# esquemabasico.net
KiCad netlist of a schematic drawn in EAGLE
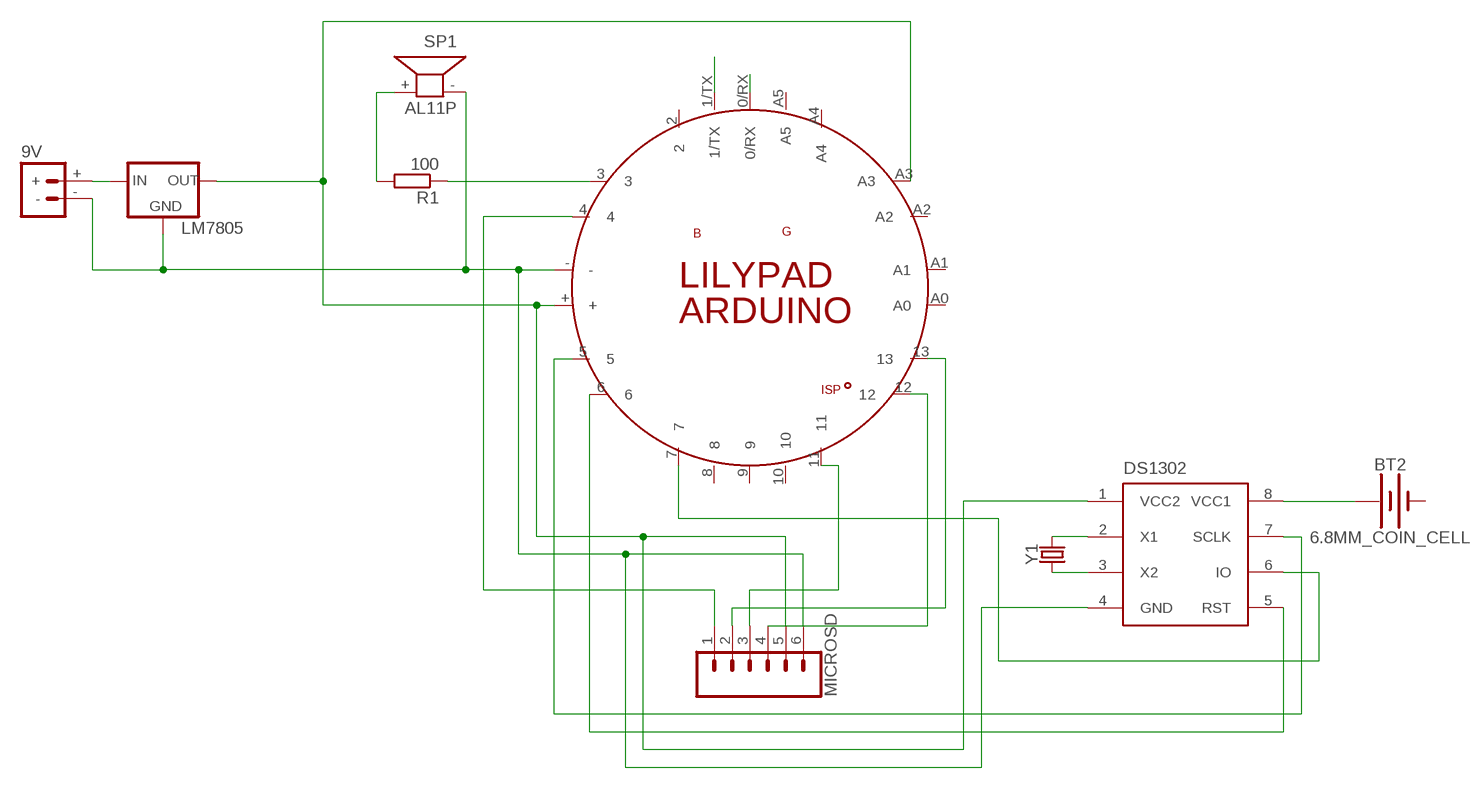
[diagram p0: schematic, sheet 1]

(export (version "E")
  (design (tool "Eeschema 10.0.6"))
  (components
    (comp (ref "9V")
      (value "BATTERY_CONN_DEANS")
      (footprint "eagle-import:DEANS")
      (libsource (lib "eagle-import") (part "BATTERY_CONN_DEANS"))
    )
    (comp (ref "BT2")
      (value "6.8MM_COIN_CELL")
      (footprint "eagle-import:BATTCON-6.8MM")
      (libsource (lib "eagle-import") (part "BATTERY-6.8MM_SMD"))
    )
    (comp (ref "DS1302")
      (value "DS1302")
      (footprint "eagle-import:PDIP8")
      (libsource (lib "eagle-import") (part "DS1302"))
    )
    (comp (ref "LM7805")
      (value "V_REG_78XX-TO-220")
      (footprint "eagle-import:TO-220-ALT")
      (libsource (lib "eagle-import") (part "V_REG_78XX-TO-220"))
    )
    (comp (ref "MICROSD")
      (value "CONN_06FEMALE_LOCK")
      (footprint "eagle-import:1X06_FEMALE_LOCK.010")
      (libsource (lib "eagle-import") (part "CONN_06FEMALE_LOCK"))
    )
    (comp (ref "PCB1")
      (value "ARDUINO_LILYPAD")
      (footprint "eagle-import:ARDUINO_LILYPAD")
      (libsource (lib "eagle-import") (part "ARDUINO_LILYPAD"))
    )
    (comp (ref "R1")
      (value "100")
      (footprint "eagle-import:0309_12")
      (libsource (lib "eagle-import") (part "R-EU_0309/12"))
    )
    (comp (ref "SP1")
      (value "AL11P")
      (footprint "eagle-import:AL11P")
      (libsource (lib "eagle-import") (part "AL11P"))
    )
    (comp (ref "Y1")
      (value "CRYSTALPTH-2X6")
      (footprint "eagle-import:CRYSTAL-PTH-2X6-CYL")
      (libsource (lib "eagle-import") (part "CRYSTALPTH-2X6"))
    )
  )
  (nets
    (net (code "1") (name "/-") (class "Default")
      (node (ref "BT2") (pin "-") (pinfunction "-_-") (pintype "power_in"))
    )
    (net (code "2") (name "Net-(9V-Pad+)") (class "Default")
      (node (ref "9V") (pin "+") (pinfunction "+_+") (pintype "passive"))
      (node (ref "LM7805") (pin "IN") (pinfunction "IN_IN") (pintype "input"))
    )
    (net (code "3") (name "Net-(DS1302-GND)") (class "Default")
      (node (ref "9V") (pin "-") (pinfunction "-_-") (pintype "passive"))
      (node (ref "DS1302") (pin "4") (pinfunction "GND_4") (pintype "power_in"))
      (node (ref "LM7805") (pin "GND") (pinfunction "GND_GND") (pintype "input"))
      (node (ref "MICROSD") (pin "6") (pinfunction "6_6") (pintype "passive"))
      (node (ref "PCB1") (pin "-") (pinfunction "-_-") (pintype "bidirectional"))
      (node (ref "SP1") (pin "-") (pinfunction "1_-") (pintype "passive"))
    )
    (net (code "4") (name "Net-(DS1302-IO)") (class "Default")
      (node (ref "DS1302") (pin "6") (pinfunction "IO_6") (pintype "bidirectional"))
      (node (ref "PCB1") (pin "7") (pinfunction "7_7") (pintype "bidirectional"))
    )
    (net (code "5") (name "Net-(DS1302-RST)") (class "Default")
      (node (ref "DS1302") (pin "5") (pinfunction "RST_5") (pintype "input"))
      (node (ref "PCB1") (pin "6") (pinfunction "6_6") (pintype "bidirectional"))
    )
    (net (code "6") (name "Net-(DS1302-SCLK)") (class "Default")
      (node (ref "DS1302") (pin "7") (pinfunction "SCLK_7") (pintype "input"))
      (node (ref "PCB1") (pin "5") (pinfunction "5_5") (pintype "bidirectional"))
    )
    (net (code "7") (name "Net-(DS1302-VCC1)") (class "Default")
      (node (ref "BT2") (pin "+") (pinfunction "+_+") (pintype "power_in"))
      (node (ref "DS1302") (pin "8") (pinfunction "VCC1_8") (pintype "power_in"))
    )
    (net (code "8") (name "Net-(DS1302-VCC2)") (class "Default")
      (node (ref "DS1302") (pin "1") (pinfunction "VCC2_1") (pintype "power_in"))
      (node (ref "LM7805") (pin "OUT") (pinfunction "OUT_OUT") (pintype "passive"))
      (node (ref "MICROSD") (pin "5") (pinfunction "5_5") (pintype "passive"))
      (node (ref "PCB1") (pin "+") (pinfunction "+_+") (pintype "bidirectional"))
      (node (ref "PCB1") (pin "A3") (pinfunction "A3_A3") (pintype "bidirectional"))
    )
    (net (code "9") (name "Net-(DS1302-X1)") (class "Default")
      (node (ref "DS1302") (pin "2") (pinfunction "X1_2") (pintype "bidirectional"))
      (node (ref "Y1") (pin "2") (pinfunction "2_2") (pintype "passive"))
    )
    (net (code "10") (name "Net-(DS1302-X2)") (class "Default")
      (node (ref "DS1302") (pin "3") (pinfunction "X2_3") (pintype "bidirectional"))
      (node (ref "Y1") (pin "1") (pinfunction "1_1") (pintype "passive"))
    )
    (net (code "11") (name "Net-(MICROSD-Pad1)") (class "Default")
      (node (ref "MICROSD") (pin "1") (pinfunction "1_1") (pintype "passive"))
      (node (ref "PCB1") (pin "4") (pinfunction "4_4") (pintype "bidirectional"))
    )
    (net (code "12") (name "Net-(MICROSD-Pad2)") (class "Default")
      (node (ref "MICROSD") (pin "2") (pinfunction "2_2") (pintype "passive"))
      (node (ref "PCB1") (pin "13") (pinfunction "13_13") (pintype "bidirectional"))
    )
    (net (code "13") (name "Net-(MICROSD-Pad3)") (class "Default")
      (node (ref "MICROSD") (pin "3") (pinfunction "3_3") (pintype "passive"))
      (node (ref "PCB1") (pin "11") (pinfunction "11_11") (pintype "bidirectional"))
    )
    (net (code "14") (name "Net-(MICROSD-Pad4)") (class "Default")
      (node (ref "MICROSD") (pin "4") (pinfunction "4_4") (pintype "passive"))
      (node (ref "PCB1") (pin "12") (pinfunction "12_12") (pintype "bidirectional"))
    )
    (net (code "15") (name "Net-(PCB1-Pad3)") (class "Default")
      (node (ref "PCB1") (pin "3") (pinfunction "3_3") (pintype "bidirectional"))
      (node (ref "R1") (pin "1") (pinfunction "1_1") (pintype "passive"))
    )
    (net (code "16") (name "Net-(SP1-2)") (class "Default")
      (node (ref "R1") (pin "2") (pinfunction "2_2") (pintype "passive"))
      (node (ref "SP1") (pin "+") (pinfunction "2_+") (pintype "passive"))
    )
    (net (code "17") (name "unconnected-(PCB1-GND-PadGND_)") (class "Default")
      (node (ref "PCB1") (pin "GND_") (pinfunction "GND_GND_") (pintype "bidirectional"))
    )
    (net (code "18") (name "unconnected-(PCB1-Pad0{slash}RX)") (class "Default")
      (node (ref "PCB1") (pin "0/RX") (pinfunction "0/RX_0/RX") (pintype "bidirectional"))
    )
    (net (code "19") (name "unconnected-(PCB1-Pad1{slash}TX)") (class "Default")
      (node (ref "PCB1") (pin "1/TX") (pinfunction "1/TX_1/TX") (pintype "bidirectional"))
    )
    (net (code "20") (name "unconnected-(PCB1-Pad2)") (class "Default")
      (node (ref "PCB1") (pin "2") (pinfunction "2_2") (pintype "bidirectional"))
    )
    (net (code "21") (name "unconnected-(PCB1-Pad8)") (class "Default")
      (node (ref "PCB1") (pin "8") (pinfunction "8_8") (pintype "bidirectional"))
    )
    (net (code "22") (name "unconnected-(PCB1-Pad9)") (class "Default")
      (node (ref "PCB1") (pin "9") (pinfunction "9_9") (pintype "bidirectional"))
    )
    (net (code "23") (name "unconnected-(PCB1-Pad10)") (class "Default")
      (node (ref "PCB1") (pin "10") (pinfunction "10_10") (pintype "bidirectional"))
    )
    (net (code "24") (name "unconnected-(PCB1-PadA0)") (class "Default")
      (node (ref "PCB1") (pin "A0") (pinfunction "A0_A0") (pintype "bidirectional"))
    )
    (net (code "25") (name "unconnected-(PCB1-PadA1)") (class "Default")
      (node (ref "PCB1") (pin "A1") (pinfunction "A1_A1") (pintype "bidirectional"))
    )
    (net (code "26") (name "unconnected-(PCB1-PadA2)") (class "Default")
      (node (ref "PCB1") (pin "A2") (pinfunction "A2_A2") (pintype "bidirectional"))
    )
    (net (code "27") (name "unconnected-(PCB1-PadA4)") (class "Default")
      (node (ref "PCB1") (pin "A4") (pinfunction "A4_A4") (pintype "bidirectional"))
    )
    (net (code "28") (name "unconnected-(PCB1-PadA5)") (class "Default")
      (node (ref "PCB1") (pin "A5") (pinfunction "A5_A5") (pintype "bidirectional"))
    )
    (net (code "29") (name "unconnected-(PCB1-PadDTR)") (class "Default")
      (node (ref "PCB1") (pin "DTR") (pinfunction "DTR_DTR") (pintype "bidirectional"))
    )
    (net (code "30") (name "unconnected-(PCB1-PadGND.)") (class "Default")
      (node (ref "PCB1") (pin "GND.") (pinfunction "GND._GND.") (pintype "bidirectional"))
    )
    (net (code "31") (name "unconnected-(PCB1-PadGND..)") (class "Default")
      (node (ref "PCB1") (pin "GND..") (pinfunction "GND.._GND..") (pintype "bidirectional"))
    )
    (net (code "32") (name "unconnected-(PCB1-PadMISO)") (class "Default")
      (node (ref "PCB1") (pin "MISO") (pinfunction "MISO_MISO") (pintype "bidirectional"))
    )
    (net (code "33") (name "unconnected-(PCB1-PadMOSI)") (class "Default")
      (node (ref "PCB1") (pin "MOSI") (pinfunction "MOSI_MOSI") (pintype "bidirectional"))
    )
    (net (code "34") (name "unconnected-(PCB1-PadRXI)") (class "Default")
      (node (ref "PCB1") (pin "RXI") (pinfunction "RXI_RXI") (pintype "bidirectional"))
    )
    (net (code "35") (name "unconnected-(PCB1-PadSCK)") (class "Default")
      (node (ref "PCB1") (pin "SCK") (pinfunction "SCK_SCK") (pintype "bidirectional"))
    )
    (net (code "36") (name "unconnected-(PCB1-PadTXO)") (class "Default")
      (node (ref "PCB1") (pin "TXO") (pinfunction "TXO_TXO") (pintype "bidirectional"))
    )
    (net (code "37") (name "unconnected-(PCB1-PadVCC.)") (class "Default")
      (node (ref "PCB1") (pin "VCC.") (pinfunction "VCC._VCC.") (pintype "bidirectional"))
    )
    (net (code "38") (name "unconnected-(PCB1-RST-PadRESET..)") (class "Default")
      (node (ref "PCB1") (pin "RESET..") (pinfunction "RST_RESET..") (pintype "bidirectional"))
    )
    (net (code "39") (name "unconnected-(PCB1-VCC-Pad5V.)") (class "Default")
      (node (ref "PCB1") (pin "5V.") (pinfunction "VCC_5V.") (pintype "bidirectional"))
    )
  )
)
